# Schematic.net
KiCad netlist of a schematic drawn in EAGLE
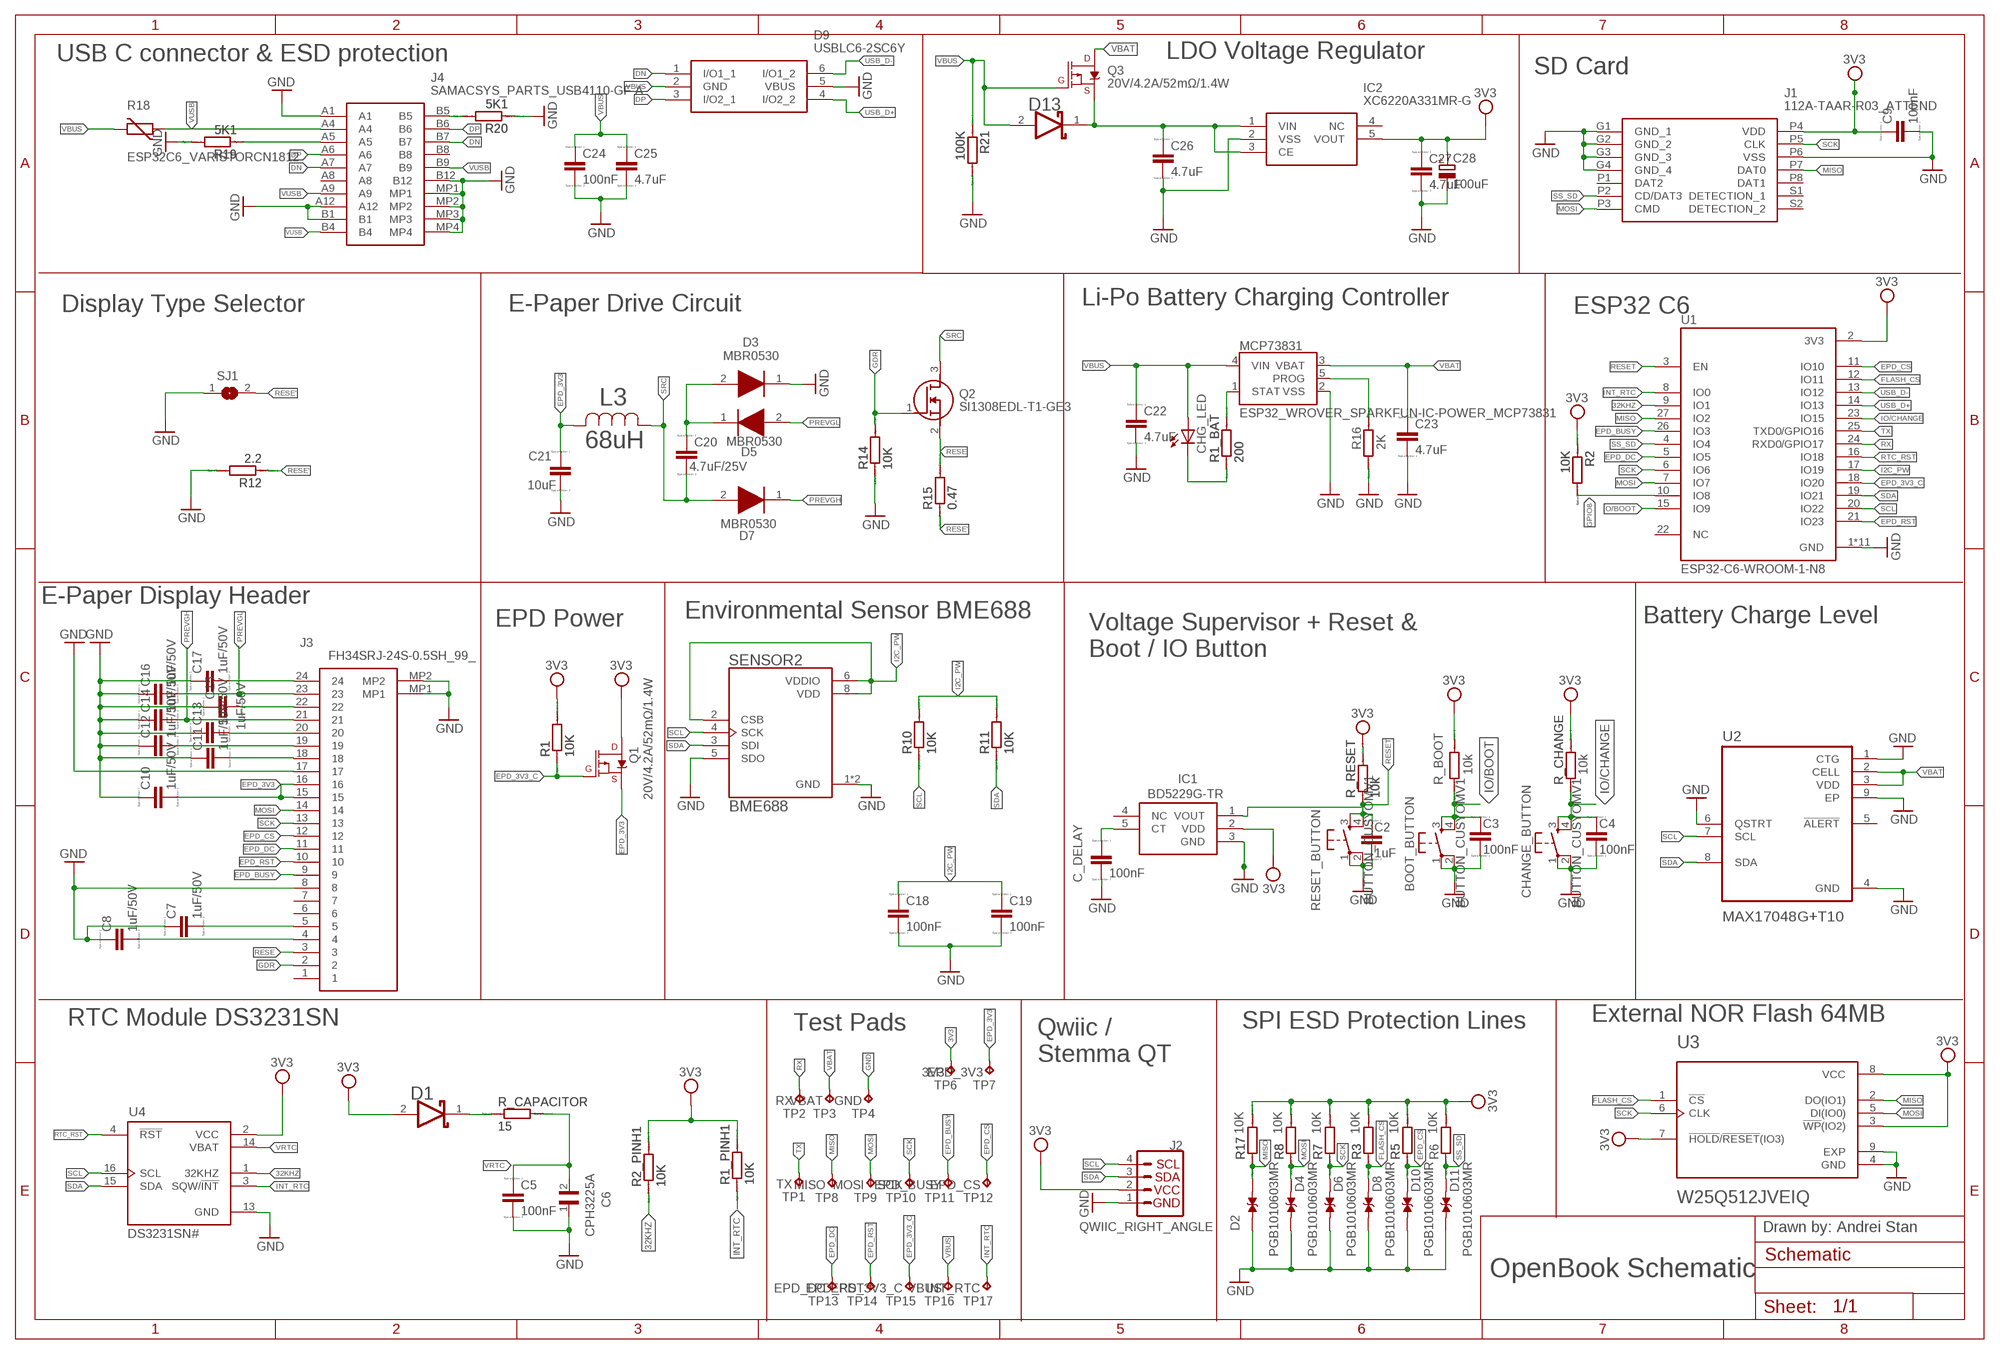
[diagram p0: schematic, sheet 1]

(export (version "E")
  (design (tool "Eeschema 10.0.6"))
  (components
    (comp (ref "BOOT_BUTTON")
      (value "BUTTON_CUSYOMV1")
      (footprint "eagle-import:MYBUTTON")
      (libsource (lib "eagle-import") (part "BUTTON_CUSYOMV1"))
    )
    (comp (ref "C2")
      (value "1uF")
      (footprint "eagle-import:EAGLE-LTSPICE_C0402")
      (libsource (lib "eagle-import") (part "EAGLE-LTSPICE_CC0402"))
    )
    (comp (ref "C3")
      (value "100nF")
      (footprint "eagle-import:EAGLE-LTSPICE_C0402")
      (libsource (lib "eagle-import") (part "EAGLE-LTSPICE_CC0402"))
    )
    (comp (ref "C4")
      (value "100nF")
      (footprint "eagle-import:EAGLE-LTSPICE_C0402")
      (libsource (lib "eagle-import") (part "EAGLE-LTSPICE_CC0402"))
    )
    (comp (ref "C5")
      (value "100nF")
      (footprint "eagle-import:EAGLE-LTSPICE_C0402")
      (libsource (lib "eagle-import") (part "EAGLE-LTSPICE_CC0402"))
    )
    (comp (ref "C6")
      (value "CPH3225A")
      (footprint "eagle-import:CAPCP3225X100N")
      (fields (field (name "MF") "Seiko Instruments"))
      (libsource (lib "eagle-import") (part "CPH3225A"))
    )
    (comp (ref "C7")
      (value "1uF/50V")
      (footprint "eagle-import:EAGLE-LTSPICE_C0402")
      (libsource (lib "eagle-import") (part "EAGLE-LTSPICE_CC0402"))
    )
    (comp (ref "C8")
      (value "1uF/50V")
      (footprint "eagle-import:EAGLE-LTSPICE_C0402")
      (libsource (lib "eagle-import") (part "EAGLE-LTSPICE_CC0402"))
    )
    (comp (ref "C9")
      (value "100nF")
      (footprint "eagle-import:EAGLE-LTSPICE_C0402")
      (libsource (lib "eagle-import") (part "EAGLE-LTSPICE_CC0402"))
    )
    (comp (ref "C10")
      (value "1uF/50V")
      (footprint "eagle-import:EAGLE-LTSPICE_C0402")
      (libsource (lib "eagle-import") (part "EAGLE-LTSPICE_CC0402"))
    )
    (comp (ref "C11")
      (value "1uF/50V")
      (footprint "eagle-import:EAGLE-LTSPICE_C0402")
      (libsource (lib "eagle-import") (part "EAGLE-LTSPICE_CC0402"))
    )
    (comp (ref "C12")
      (value "1uF/50V")
      (footprint "eagle-import:EAGLE-LTSPICE_C0402")
      (libsource (lib "eagle-import") (part "EAGLE-LTSPICE_CC0402"))
    )
    (comp (ref "C13")
      (value "1uF/50V")
      (footprint "eagle-import:EAGLE-LTSPICE_C0402")
      (libsource (lib "eagle-import") (part "EAGLE-LTSPICE_CC0402"))
    )
    (comp (ref "C14")
      (value "1uF/50V")
      (footprint "eagle-import:EAGLE-LTSPICE_C0402")
      (libsource (lib "eagle-import") (part "EAGLE-LTSPICE_CC0402"))
    )
    (comp (ref "C15")
      (value "1uF/50V")
      (footprint "eagle-import:EAGLE-LTSPICE_C0402")
      (libsource (lib "eagle-import") (part "EAGLE-LTSPICE_CC0402"))
    )
    (comp (ref "C16")
      (value "1uF/50V")
      (footprint "eagle-import:EAGLE-LTSPICE_C0402")
      (libsource (lib "eagle-import") (part "EAGLE-LTSPICE_CC0402"))
    )
    (comp (ref "C17")
      (value "1uF/50V")
      (footprint "eagle-import:EAGLE-LTSPICE_C0402")
      (libsource (lib "eagle-import") (part "EAGLE-LTSPICE_CC0402"))
    )
    (comp (ref "C18")
      (value "100nF")
      (footprint "eagle-import:EAGLE-LTSPICE_C0402")
      (libsource (lib "eagle-import") (part "EAGLE-LTSPICE_CC0402"))
    )
    (comp (ref "C19")
      (value "100nF")
      (footprint "eagle-import:EAGLE-LTSPICE_C0402")
      (libsource (lib "eagle-import") (part "EAGLE-LTSPICE_CC0402"))
    )
    (comp (ref "C20")
      (value "4.7uF/25V")
      (footprint "eagle-import:ESP32_WROVER_EAGLE-LTSPICE_C0402")
      (libsource (lib "eagle-import") (part "ESP32_WROVER_EAGLE-LTSPICE_CC0402"))
    )
    (comp (ref "C21")
      (value "10uF")
      (footprint "eagle-import:ESP32_WROVER_EAGLE-LTSPICE_C0402")
      (libsource (lib "eagle-import") (part "ESP32_WROVER_EAGLE-LTSPICE_CC0402"))
    )
    (comp (ref "C22")
      (value "4.7uF")
      (footprint "eagle-import:EAGLE-LTSPICE_C0402")
      (libsource (lib "eagle-import") (part "EAGLE-LTSPICE_CC0402"))
    )
    (comp (ref "C23")
      (value "4.7uF")
      (footprint "eagle-import:EAGLE-LTSPICE_C0402")
      (libsource (lib "eagle-import") (part "EAGLE-LTSPICE_CC0402"))
    )
    (comp (ref "C24")
      (value "100nF")
      (footprint "eagle-import:ESP32_WROVER_EAGLE-LTSPICE_C0402")
      (libsource (lib "eagle-import") (part "ESP32_WROVER_EAGLE-LTSPICE_CC0402"))
    )
    (comp (ref "C25")
      (value "4.7uF")
      (footprint "eagle-import:ESP32_WROVER_EAGLE-LTSPICE_C0402")
      (libsource (lib "eagle-import") (part "ESP32_WROVER_EAGLE-LTSPICE_CC0402"))
    )
    (comp (ref "C26")
      (value "4.7uF")
      (footprint "eagle-import:ESP32_WROVER_EAGLE-LTSPICE_C0402")
      (libsource (lib "eagle-import") (part "ESP32_WROVER_EAGLE-LTSPICE_CC0402"))
    )
    (comp (ref "C27")
      (value "4.7uF")
      (footprint "eagle-import:ESP32_WROVER_EAGLE-LTSPICE_C0402")
      (libsource (lib "eagle-import") (part "ESP32_WROVER_EAGLE-LTSPICE_CC0402"))
    )
    (comp (ref "C28")
      (value "100uF")
      (footprint "eagle-import:RCL_CT3528")
      (libsource (lib "eagle-import") (part "RCL_CPOL-EUCT3528"))
    )
    (comp (ref "CHANGE_BUTTON")
      (value "BUTTON_CUSYOMV1")
      (footprint "eagle-import:MYBUTTON")
      (libsource (lib "eagle-import") (part "BUTTON_CUSYOMV1"))
    )
    (comp (ref "CHG_LED")
      (value "ADAFRUIT_LEDCHIP-LED0603")
      (footprint "eagle-import:ADAFRUIT_CHIP-LED0603")
      (libsource (lib "eagle-import") (part "ADAFRUIT_LEDCHIP-LED0603"))
    )
    (comp (ref "C_DELAY")
      (value "100nF")
      (footprint "eagle-import:EAGLE-LTSPICE_C0402")
      (libsource (lib "eagle-import") (part "EAGLE-LTSPICE_CC0402"))
    )
    (comp (ref "D1")
      (value "ESP32_WROVER_AVX---SD0805S020S1R0_AVX_SD0805S020S1R0_0_0AVX_SD0805S020S1R0_0_0")
      (footprint "eagle-import:ESP32_WROVER_AVX---SD0805S020S1R0_AVX_SD0805S020S1R0_0")
      (fields
        (field (name "DIGIKEY_PART_NUMBER") "478-7800-1-ND")
        (field (name "MF") "AVX")
        (field (name "MOUSER_PART_NUMBER") "581-SD0805S020S1R0")
      )
      (libsource (lib "eagle-import") (part "ESP32_WROVER_AVX---SD0805S020S1R0_AVX_SD0805S020S1R0_0_0AVX_SD0805S020S1R0_0_0"))
    )
    (comp (ref "D2")
      (value "PGB1010603MR")
      (footprint "eagle-import:DIOC1608X36N")
      (fields (field (name "MF") "Littelfuse Inc."))
      (libsource (lib "eagle-import") (part "PGB1010603MR"))
    )
    (comp (ref "D3")
      (value "MBR0530")
      (footprint "eagle-import:SOD3716X135N")
      (fields (field (name "MF") "ON Semiconductor"))
      (libsource (lib "eagle-import") (part "MBR0530"))
    )
    (comp (ref "D4")
      (value "PGB1010603MR")
      (footprint "eagle-import:DIOC1608X36N")
      (fields (field (name "MF") "Littelfuse Inc."))
      (libsource (lib "eagle-import") (part "PGB1010603MR"))
    )
    (comp (ref "D5")
      (value "MBR0530")
      (footprint "eagle-import:SOD3716X135N")
      (fields (field (name "MF") "ON Semiconductor"))
      (libsource (lib "eagle-import") (part "MBR0530"))
    )
    (comp (ref "D6")
      (value "PGB1010603MR")
      (footprint "eagle-import:DIOC1608X36N")
      (fields (field (name "MF") "Littelfuse Inc."))
      (libsource (lib "eagle-import") (part "PGB1010603MR"))
    )
    (comp (ref "D7")
      (value "MBR0530")
      (footprint "eagle-import:SOD3716X135N")
      (fields (field (name "MF") "ON Semiconductor"))
      (libsource (lib "eagle-import") (part "MBR0530"))
    )
    (comp (ref "D8")
      (value "PGB1010603MR")
      (footprint "eagle-import:DIOC1608X36N")
      (fields (field (name "MF") "Littelfuse Inc."))
      (libsource (lib "eagle-import") (part "PGB1010603MR"))
    )
    (comp (ref "D9")
      (value "USBLC6-2SC6Y")
      (footprint "eagle-import:SOT95P280X145-6N")
      (fields (field (name "MF") "STMicroelectronics"))
      (libsource (lib "eagle-import") (part "USBLC6-2SC6Y"))
    )
    (comp (ref "D10")
      (value "PGB1010603MR")
      (footprint "eagle-import:DIOC1608X36N")
      (fields (field (name "MF") "Littelfuse Inc."))
      (libsource (lib "eagle-import") (part "PGB1010603MR"))
    )
    (comp (ref "D11")
      (value "PGB1010603MR")
      (footprint "eagle-import:DIOC1608X36N")
      (fields (field (name "MF") "Littelfuse Inc."))
      (libsource (lib "eagle-import") (part "PGB1010603MR"))
    )
    (comp (ref "D13")
      (value "ESP32_WROVER_AVX---SD0805S020S1R0_AVX_SD0805S020S1R0_0_0AVX_SD0805S020S1R0_0_0")
      (footprint "eagle-import:ESP32_WROVER_AVX---SD0805S020S1R0_AVX_SD0805S020S1R0_0")
      (fields
        (field (name "DIGIKEY_PART_NUMBER") "478-7800-1-ND")
        (field (name "MF") "AVX")
        (field (name "MOUSER_PART_NUMBER") "581-SD0805S020S1R0")
      )
      (libsource (lib "eagle-import") (part "DeskAssistant v19 v2_vf.c-uWg7zGRE2SlFihlENo6g_ESP32_WROVER_AVX---SD0805S020S1R0_AVX_SD0805S020S1R0_0_0AVX_SD0805S020S1R0_0_0"))
    )
    (comp (ref "IC1")
      (value "BD5229G-TR")
      (footprint "eagle-import:SOT95P280X125-5N")
      (fields (field (name "MOUSER_PART_NUMBER") "755-BD5229G-TR"))
      (libsource (lib "eagle-import") (part "BD5229G-TR"))
    )
    (comp (ref "IC2")
      (value "XC6220A331MR-G")
      (footprint "eagle-import:SOT95P280X120-5N")
      (fields (field (name "MOUSER_PART_NUMBER") "865-XC6220A331MR-G"))
      (libsource (lib "eagle-import") (part "XC6220A331MR-G"))
    )
    (comp (ref "J1")
      (value "112A-TAAR-R03_ATTEND")
      (footprint "eagle-import:112ATAARR03ATTEND")
      (fields (field (name "MANUFACTURER_PART_NUMBER") "112A-TAAR-R03 ATTEND"))
      (libsource (lib "eagle-import") (part "112A-TAAR-R03_ATTEND"))
    )
    (comp (ref "J2")
      (value "QWIIC_RIGHT_ANGLE")
      (footprint "eagle-import:JST04_1MM_RA")
      (libsource (lib "eagle-import") (part "QWIIC_CONNECTORJS-1MM"))
    )
    (comp (ref "J3")
      (value "FH34SRJ-24S-0.5SH_99_")
      (footprint "eagle-import:FH34SRJ24S05SH99")
      (fields
        (field (name "MANUFACTURER_PART_NUMBER") "FH34SRJ-24S-0.5SH(99)")
        (field (name "MOUSER_PART_NUMBER") "798-FH34SRJ24S05SH99")
      )
      (libsource (lib "eagle-import") (part "FH34SRJ-24S-0.5SH_99_"))
    )
    (comp (ref "J4")
      (value "SAMACSYS_PARTS_USB4110-GF-A")
      (footprint "eagle-import:SAMACSYS_PARTS_USB4110GFA")
      (fields
        (field (name "MANUFACTURER_PART_NUMBER") "USB4110-GF-A")
        (field (name "MOUSER_PART_NUMBER") "640-USB4110-GF-A")
      )
      (libsource (lib "eagle-import") (part "SAMACSYS_PARTS_USB4110-GF-A"))
    )
    (comp (ref "L3")
      (value "68uH")
      (footprint "eagle-import:IND_4828-WE-TPC_WRE")
      (fields
        (field (name "MANUFACTURER_PART_NUMBER") "744043680")
        (field (name "COPYRIGHT") "Copyright (C) 2024 Ultra Librarian. All rights reserved.")
      )
      (libsource (lib "eagle-import") (part "744043680IND_4828-WE-TPC_WRE"))
    )
    (comp (ref "MCP73831")
      (value "ESP32_WROVER_SPARKFUN-IC-POWER_MCP73831")
      (footprint "eagle-import:ESP32_WROVER_SPARKFUN-IC-POWER_SOT23-5")
      (libsource (lib "eagle-import") (part "ESP32_WROVER_SPARKFUN-IC-POWER_MCP73831"))
    )
    (comp (ref "Q1")
      (value "20V/4.2A/52mΩ/1.4W")
      (footprint "eagle-import:ESP32_WROVER_SPARKFUN-DISCRETESEMI_SOT23-3")
      (libsource (lib "eagle-import") (part "ESP32_WROVER_SPARKFUN-DISCRETESEMI_MOSFET_PCH-DMG2305UX-7"))
    )
    (comp (ref "Q2")
      (value "SI1308EDL-T1-GE3")
      (footprint "eagle-import:SOT65P210X110-3N")
      (fields (field (name "MF") "Vishay Siliconix"))
      (libsource (lib "eagle-import") (part "SI1308EDL-T1-GE3"))
    )
    (comp (ref "Q3")
      (value "20V/4.2A/52mΩ/1.4W")
      (footprint "eagle-import:ESP32_WROVER_SPARKFUN-DISCRETESEMI_SOT23-3")
      (libsource (lib "eagle-import") (part "DeskAssistant v19 v2_vf.c-uWg7zGRE2SlFihlENo6g_ESP32_WROVER_SPARKFUN-DISCRETESEMI_MOSFET_PCH-DMG2305UX-7"))
    )
    (comp (ref "R1")
      (value "10K")
      (footprint "eagle-import:ESP32_WROVER_EAGLE-LTSPICE_R0402")
      (libsource (lib "eagle-import") (part "ESP32_WROVER_EAGLE-LTSPICE_RR0402"))
    )
    (comp (ref "R1_BAT")
      (value "200")
      (footprint "eagle-import:ESP32_WROVER_EAGLE-LTSPICE_R0402")
      (libsource (lib "eagle-import") (part "ESP32_WROVER_EAGLE-LTSPICE_RR0402"))
    )
    (comp (ref "R1_PINH1")
      (value "10K")
      (footprint "eagle-import:ESP32_WROVER_EAGLE-LTSPICE_R0402")
      (libsource (lib "eagle-import") (part "ESP32_WROVER_EAGLE-LTSPICE_RR0402"))
    )
    (comp (ref "R2")
      (value "10K")
      (footprint "eagle-import:ESP32_WROVER_EAGLE-LTSPICE_R0402")
      (libsource (lib "eagle-import") (part "ESP32_WROVER_EAGLE-LTSPICE_RR0402"))
    )
    (comp (ref "R2_PINH1")
      (value "10K")
      (footprint "eagle-import:ESP32_WROVER_EAGLE-LTSPICE_R0402")
      (libsource (lib "eagle-import") (part "ESP32_WROVER_EAGLE-LTSPICE_RR0402"))
    )
    (comp (ref "R3")
      (value "10K")
      (footprint "eagle-import:ESP32_WROVER_EAGLE-LTSPICE_R0402")
      (libsource (lib "eagle-import") (part "ESP32_WROVER_EAGLE-LTSPICE_RR0402"))
    )
    (comp (ref "R5")
      (value "10K")
      (footprint "eagle-import:ESP32_WROVER_EAGLE-LTSPICE_R0402")
      (libsource (lib "eagle-import") (part "ESP32_WROVER_EAGLE-LTSPICE_RR0402"))
    )
    (comp (ref "R6")
      (value "10K")
      (footprint "eagle-import:ESP32_WROVER_EAGLE-LTSPICE_R0402")
      (libsource (lib "eagle-import") (part "ESP32_WROVER_EAGLE-LTSPICE_RR0402"))
    )
    (comp (ref "R7")
      (value "10K")
      (footprint "eagle-import:ESP32_WROVER_EAGLE-LTSPICE_R0402")
      (libsource (lib "eagle-import") (part "ESP32_WROVER_EAGLE-LTSPICE_RR0402"))
    )
    (comp (ref "R8")
      (value "10K")
      (footprint "eagle-import:ESP32_WROVER_EAGLE-LTSPICE_R0402")
      (libsource (lib "eagle-import") (part "ESP32_WROVER_EAGLE-LTSPICE_RR0402"))
    )
    (comp (ref "R10")
      (value "10K")
      (footprint "eagle-import:ESP32_WROVER_EAGLE-LTSPICE_R0402")
      (libsource (lib "eagle-import") (part "ESP32_WROVER_EAGLE-LTSPICE_RR0402"))
    )
    (comp (ref "R11")
      (value "10K")
      (footprint "eagle-import:ESP32_WROVER_EAGLE-LTSPICE_R0402")
      (libsource (lib "eagle-import") (part "ESP32_WROVER_EAGLE-LTSPICE_RR0402"))
    )
    (comp (ref "R12")
      (value "2.2")
      (footprint "eagle-import:ESP32_WROVER_EAGLE-LTSPICE_R0402")
      (libsource (lib "eagle-import") (part "ESP32_WROVER_EAGLE-LTSPICE_RR0402"))
    )
    (comp (ref "R14")
      (value "10K")
      (footprint "eagle-import:ESP32_WROVER_EAGLE-LTSPICE_R0402")
      (libsource (lib "eagle-import") (part "DeskAssistant v19 v2_vf.c-uWg7zGRE2SlFihlENo6g_ESP32_WROVER_EAGLE-LTSPICE_RR0402"))
    )
    (comp (ref "R15")
      (value "0.47")
      (footprint "eagle-import:ESP32_WROVER_EAGLE-LTSPICE_R0402")
      (libsource (lib "eagle-import") (part "DeskAssistant v19 v2_vf.c-uWg7zGRE2SlFihlENo6g_ESP32_WROVER_EAGLE-LTSPICE_RR0402"))
    )
    (comp (ref "R16")
      (value "2K")
      (footprint "eagle-import:ESP32_WROVER_EAGLE-LTSPICE_R0402")
      (libsource (lib "eagle-import") (part "ESP32_WROVER_EAGLE-LTSPICE_RR0402"))
    )
    (comp (ref "R17")
      (value "10K")
      (footprint "eagle-import:ESP32_WROVER_EAGLE-LTSPICE_R0402")
      (libsource (lib "eagle-import") (part "ESP32_WROVER_EAGLE-LTSPICE_RR0402"))
    )
    (comp (ref "R18")
      (value "ESP32C6_VARISTORCN1812")
      (footprint "eagle-import:ESP32C6_VARISTOR_CT_CN1812")
      (libsource (lib "eagle-import") (part "ESP32C6_VARISTORCN1812"))
    )
    (comp (ref "R19")
      (value "5K1")
      (footprint "eagle-import:ESP32_WROVER_EAGLE-LTSPICE_R0402")
      (libsource (lib "eagle-import") (part "ESP32_WROVER_EAGLE-LTSPICE_RR0402"))
    )
    (comp (ref "R20")
      (value "5K1")
      (footprint "eagle-import:ESP32_WROVER_EAGLE-LTSPICE_R0402")
      (libsource (lib "eagle-import") (part "ESP32_WROVER_EAGLE-LTSPICE_RR0402"))
    )
    (comp (ref "R21")
      (value "100K")
      (footprint "eagle-import:ESP32_WROVER_EAGLE-LTSPICE_R0402")
      (libsource (lib "eagle-import") (part "ESP32_WROVER_EAGLE-LTSPICE_RR0402"))
    )
    (comp (ref "RESET_BUTTON")
      (value "BUTTON_CUSYOMV1")
      (footprint "eagle-import:MYBUTTON")
      (fields
        (field (name "MOUSER_PRICE-STOCK") "https://ro.mouser.com/ProductDetail/Panasonic/EVQ-9P701P?qs=NPkb10g2yLBKCwpELvsGNg%3D%3D")
      )
      (libsource (lib "eagle-import") (part "BUTTON_CUSYOMV1"))
    )
    (comp (ref "R_BOOT")
      (value "10k")
      (footprint "eagle-import:ESP32_WROVER_EAGLE-LTSPICE_R0402")
      (libsource (lib "eagle-import") (part "ESP32_WROVER_EAGLE-LTSPICE_RR0402"))
    )
    (comp (ref "R_CAPACITOR")
      (value "15")
      (footprint "eagle-import:ESP32_WROVER_EAGLE-LTSPICE_R0402")
      (libsource (lib "eagle-import") (part "ESP32_WROVER_EAGLE-LTSPICE_RR0402"))
    )
    (comp (ref "R_CHANGE")
      (value "10k")
      (footprint "eagle-import:ESP32_WROVER_EAGLE-LTSPICE_R0402")
      (libsource (lib "eagle-import") (part "ESP32_WROVER_EAGLE-LTSPICE_RR0402"))
    )
    (comp (ref "R_RESET")
      (value "10k")
      (footprint "eagle-import:ESP32_WROVER_EAGLE-LTSPICE_R0402")
      (libsource (lib "eagle-import") (part "ESP32_WROVER_EAGLE-LTSPICE_RR0402"))
    )
    (comp (ref "SENSOR2")
      (value "BME688")
      (footprint "eagle-import:ESP32_WROVER_BME680_PSON80P300X300X100-8N")
      (fields (field (name "MF") "Bosch Sensortec") (field (name "MP") "BME680"))
      (libsource (lib "eagle-import") (part "ESP32_WROVER_BME680_BME680"))
    )
    (comp (ref "SJ1") (value "SJ") (footprint "eagle-import:SJ") (libsource (lib "eagle-import") (part "SJ")))
    (comp (ref "TP1")
      (value "TPTP20R")
      (footprint "eagle-import:TP20R")
      (fields (field (name "TP_SIGNAL_NAME") "TX"))
      (libsource (lib "eagle-import") (part "TPTP20R"))
    )
    (comp (ref "TP2")
      (value "TPTP20R")
      (footprint "eagle-import:TP20R")
      (fields (field (name "TP_SIGNAL_NAME") "RX"))
      (libsource (lib "eagle-import") (part "TPTP20R"))
    )
    (comp (ref "TP3")
      (value "TPTP20R")
      (footprint "eagle-import:TP20R")
      (fields (field (name "TP_SIGNAL_NAME") "VBAT"))
      (libsource (lib "eagle-import") (part "TPTP20R"))
    )
    (comp (ref "TP4")
      (value "TPTP20R")
      (footprint "eagle-import:TP20R")
      (fields (field (name "TP_SIGNAL_NAME") "GND"))
      (libsource (lib "eagle-import") (part "TPTP20R"))
    )
    (comp (ref "TP6")
      (value "TPTP20R")
      (footprint "eagle-import:TP20R")
      (fields (field (name "TP_SIGNAL_NAME") "3V3"))
      (libsource (lib "eagle-import") (part "TPTP20R"))
    )
    (comp (ref "TP7")
      (value "TPTP20R")
      (footprint "eagle-import:TP20R")
      (fields (field (name "TP_SIGNAL_NAME") "EPD_3V3"))
      (libsource (lib "eagle-import") (part "TPTP20R"))
    )
    (comp (ref "TP8")
      (value "TPTP20R")
      (footprint "eagle-import:TP20R")
      (fields (field (name "TP_SIGNAL_NAME") "MISO"))
      (libsource (lib "eagle-import") (part "TPTP20R"))
    )
    (comp (ref "TP9")
      (value "TPTP20R")
      (footprint "eagle-import:TP20R")
      (fields (field (name "TP_SIGNAL_NAME") "MOSI"))
      (libsource (lib "eagle-import") (part "TPTP20R"))
    )
    (comp (ref "TP10")
      (value "TPTP20R")
      (footprint "eagle-import:TP20R")
      (fields (field (name "TP_SIGNAL_NAME") "SCK"))
      (libsource (lib "eagle-import") (part "TPTP20R"))
    )
    (comp (ref "TP11")
      (value "TPTP20R")
      (footprint "eagle-import:TP20R")
      (fields (field (name "TP_SIGNAL_NAME") "EPD_BUSY"))
      (libsource (lib "eagle-import") (part "TPTP20R"))
    )
    (comp (ref "TP12")
      (value "TPTP20R")
      (footprint "eagle-import:TP20R")
      (fields (field (name "TP_SIGNAL_NAME") "EPD_CS"))
      (libsource (lib "eagle-import") (part "TPTP20R"))
    )
    (comp (ref "TP13")
      (value "TPTP20R")
      (footprint "eagle-import:TP20R")
      (fields (field (name "TP_SIGNAL_NAME") "EPD_DC"))
      (libsource (lib "eagle-import") (part "TPTP20R"))
    )
    (comp (ref "TP14")
      (value "TPTP20R")
      (footprint "eagle-import:TP20R")
      (fields (field (name "TP_SIGNAL_NAME") "EPD_RST"))
      (libsource (lib "eagle-import") (part "TPTP20R"))
    )
    (comp (ref "TP15")
      (value "TPTP20R")
      (footprint "eagle-import:TP20R")
      (fields (field (name "TP_SIGNAL_NAME") "EPD_3V3_C"))
      (libsource (lib "eagle-import") (part "TPTP20R"))
    )
    (comp (ref "TP16")
      (value "TPTP20R")
      (footprint "eagle-import:TP20R")
      (fields (field (name "TP_SIGNAL_NAME") "VBUS"))
      (libsource (lib "eagle-import") (part "TPTP20R"))
    )
    (comp (ref "TP17")
      (value "TPTP20R")
      (footprint "eagle-import:TP20R")
      (fields (field (name "TP_SIGNAL_NAME") "INT_RTC"))
      (libsource (lib "eagle-import") (part "TPTP20R"))
    )
    (comp (ref "U1")
      (value "ESP32-C6-WROOM-1-N8")
      (footprint "eagle-import:XCVR_ESP32-C6-WROOM-1-N8")
      (fields (field (name "MF") "Espressif Systems"))
      (libsource (lib "eagle-import") (part "ESP32-C6-WROOM-1-N8"))
    )
    (comp (ref "U2")
      (value "MAX17048G+T10")
      (footprint "eagle-import:SON50P200X200X80-9N")
      (fields (field (name "MF") "Analog Devices"))
      (libsource (lib "eagle-import") (part "MAX17048G+T10"))
    )
    (comp (ref "U3")
      (value "W25Q512JVEIQ")
      (footprint "eagle-import:SON127P600X800X80-9N")
      (fields (field (name "MF") "Winbond Electronics"))
      (libsource (lib "eagle-import") (part "W25Q512JVEIQ"))
    )
    (comp (ref "U4")
      (value "DS3231SN#")
      (footprint "eagle-import:SOIC127P1032X265-16N")
      (fields (field (name "MF") "Analog Devices"))
      (libsource (lib "eagle-import") (part "DS3231SN#"))
    )
  )
  (nets
    (net (code "1") (name "3V3") (class "Default")
      (node (ref "C27") (pin "1") (pinfunction "1_1") (pintype "passive"))
      (node (ref "C28") (pin "+") (pinfunction "+_+") (pintype "passive"))
      (node (ref "C9") (pin "1") (pinfunction "1_1") (pintype "passive"))
      (node (ref "D1") (pin "2") (pinfunction "ANODE_2") (pintype "bidirectional"))
      (node (ref "IC1") (pin "2") (pinfunction "VDD_2") (pintype "bidirectional"))
      (node (ref "IC2") (pin "5") (pinfunction "VOUT_5") (pintype "bidirectional"))
      (node (ref "J1") (pin "P4") (pinfunction "VDD_P4") (pintype "bidirectional"))
      (node (ref "J2") (pin "2") (pinfunction "2_2") (pintype "power_in"))
      (node (ref "Q1") (pin "3") (pinfunction "D_3") (pintype "bidirectional"))
      (node (ref "R1") (pin "2") (pinfunction "2_2") (pintype "passive"))
      (node (ref "R17") (pin "2") (pinfunction "2_2") (pintype "passive"))
      (node (ref "R1_PINH1") (pin "2") (pinfunction "2_2") (pintype "passive"))
      (node (ref "R2") (pin "1") (pinfunction "1_1") (pintype "passive"))
      (node (ref "R2_PINH1") (pin "2") (pinfunction "2_2") (pintype "passive"))
      (node (ref "R3") (pin "2") (pinfunction "2_2") (pintype "passive"))
      (node (ref "R5") (pin "2") (pinfunction "2_2") (pintype "passive"))
      (node (ref "R6") (pin "2") (pinfunction "2_2") (pintype "passive"))
      (node (ref "R7") (pin "2") (pinfunction "2_2") (pintype "passive"))
      (node (ref "R8") (pin "2") (pinfunction "2_2") (pintype "passive"))
      (node (ref "R_BOOT") (pin "2") (pinfunction "2_2") (pintype "passive"))
      (node (ref "R_CHANGE") (pin "2") (pinfunction "2_2") (pintype "passive"))
      (node (ref "R_RESET") (pin "2") (pinfunction "2_2") (pintype "passive"))
      (node (ref "TP6") (pin "TP") (pinfunction "TP_TP") (pintype "input"))
      (node (ref "U1") (pin "2") (pinfunction "3V3_2") (pintype "power_in"))
      (node (ref "U3") (pin "3") (pinfunction "~{WP}(IO2)_3") (pintype "bidirectional"))
      (node (ref "U3") (pin "7") (pinfunction "~{HOLD}/~{RESET}(IO3)_7") (pintype "bidirectional"))
      (node (ref "U3") (pin "8") (pinfunction "VCC_8") (pintype "power_in"))
      (node (ref "U4") (pin "2") (pinfunction "VCC_2") (pintype "power_in"))
    )
    (net (code "2") (name "32KHZ") (class "Default")
      (node (ref "R2_PINH1") (pin "1") (pinfunction "1_1") (pintype "passive"))
      (node (ref "U1") (pin "9") (pinfunction "IO1_9") (pintype "bidirectional"))
      (node (ref "U4") (pin "1") (pinfunction "32KHZ_1") (pintype "output"))
    )
    (net (code "3") (name "DN") (class "Default")
      (node (ref "D9") (pin "1") (pinfunction "I/O1_1_1") (pintype "bidirectional"))
      (node (ref "J4") (pin "A7") (pinfunction "A7_A7") (pintype "bidirectional"))
      (node (ref "J4") (pin "B7") (pinfunction "B7_B7") (pintype "bidirectional"))
    )
    (net (code "4") (name "DP") (class "Default")
      (node (ref "D9") (pin "3") (pinfunction "I/O2_1_3") (pintype "bidirectional"))
      (node (ref "J4") (pin "A6") (pinfunction "A6_A6") (pintype "bidirectional"))
      (node (ref "J4") (pin "B6") (pinfunction "B6_B6") (pintype "bidirectional"))
    )
    (net (code "5") (name "EPD_3V3") (class "Default")
      (node (ref "C10") (pin "2") (pinfunction "2_2") (pintype "passive"))
      (node (ref "C21") (pin "1") (pinfunction "1_1") (pintype "passive"))
      (node (ref "J3") (pin "15") (pinfunction "15_15") (pintype "bidirectional"))
      (node (ref "J3") (pin "16") (pinfunction "16_16") (pintype "bidirectional"))
      (node (ref "L3") (pin "2") (pinfunction "2_2") (pintype "passive"))
      (node (ref "Q1") (pin "2") (pinfunction "S_2") (pintype "bidirectional"))
      (node (ref "TP7") (pin "TP") (pinfunction "TP_TP") (pintype "input"))
    )
    (net (code "6") (name "EPD_3V3_C") (class "Default")
      (node (ref "Q1") (pin "1") (pinfunction "G_1") (pintype "bidirectional"))
      (node (ref "R1") (pin "1") (pinfunction "1_1") (pintype "passive"))
      (node (ref "TP15") (pin "TP") (pinfunction "TP_TP") (pintype "input"))
      (node (ref "U1") (pin "18") (pinfunction "IO20_18") (pintype "bidirectional"))
    )
    (net (code "7") (name "EPD_BUSY") (class "Default")
      (node (ref "J3") (pin "9") (pinfunction "9_9") (pintype "bidirectional"))
      (node (ref "TP11") (pin "TP") (pinfunction "TP_TP") (pintype "input"))
      (node (ref "U1") (pin "26") (pinfunction "IO3_26") (pintype "bidirectional"))
    )
    (net (code "8") (name "EPD_CS") (class "Default")
      (node (ref "D10") (pin "2") (pinfunction "2_2") (pintype "passive"))
      (node (ref "J3") (pin "12") (pinfunction "12_12") (pintype "bidirectional"))
      (node (ref "R5") (pin "1") (pinfunction "1_1") (pintype "passive"))
      (node (ref "TP12") (pin "TP") (pinfunction "TP_TP") (pintype "input"))
      (node (ref "U1") (pin "11") (pinfunction "IO10_11") (pintype "bidirectional"))
    )
    (net (code "9") (name "EPD_DC") (class "Default")
      (node (ref "J3") (pin "11") (pinfunction "11_11") (pintype "bidirectional"))
      (node (ref "TP13") (pin "TP") (pinfunction "TP_TP") (pintype "input"))
      (node (ref "U1") (pin "5") (pinfunction "IO5_5") (pintype "bidirectional"))
    )
    (net (code "10") (name "EPD_RST") (class "Default")
      (node (ref "J3") (pin "10") (pinfunction "10_10") (pintype "bidirectional"))
      (node (ref "TP14") (pin "TP") (pinfunction "TP_TP") (pintype "input"))
      (node (ref "U1") (pin "21") (pinfunction "IO23_21") (pintype "bidirectional"))
    )
    (net (code "11") (name "FLASH_CS") (class "Default")
      (node (ref "D8") (pin "2") (pinfunction "2_2") (pintype "passive"))
      (node (ref "R3") (pin "1") (pinfunction "1_1") (pintype "passive"))
      (node (ref "U1") (pin "12") (pinfunction "IO11_12") (pintype "bidirectional"))
      (node (ref "U3") (pin "1") (pinfunction "~{CS}_1") (pintype "input"))
    )
    (net (code "12") (name "GDR") (class "Default")
      (node (ref "J3") (pin "2") (pinfunction "2_2") (pintype "bidirectional"))
      (node (ref "Q2") (pin "1") (pinfunction "G_1") (pintype "bidirectional"))
      (node (ref "R14") (pin "2") (pinfunction "2_2") (pintype "passive"))
    )
    (net (code "13") (name "GND") (class "Default")
      (node (ref "BOOT_BUTTON") (pin "1") (pinfunction "1_1") (pintype "passive"))
      (node (ref "BOOT_BUTTON") (pin "2") (pinfunction "2_2") (pintype "passive"))
      (node (ref "C10") (pin "1") (pinfunction "1_1") (pintype "passive"))
      (node (ref "C11") (pin "1") (pinfunction "1_1") (pintype "passive"))
      (node (ref "C12") (pin "1") (pinfunction "1_1") (pintype "passive"))
      (node (ref "C13") (pin "1") (pinfunction "1_1") (pintype "passive"))
      (node (ref "C14") (pin "1") (pinfunction "1_1") (pintype "passive"))
      (node (ref "C15") (pin "1") (pinfunction "1_1") (pintype "passive"))
      (node (ref "C16") (pin "1") (pinfunction "1_1") (pintype "passive"))
      (node (ref "C17") (pin "1") (pinfunction "1_1") (pintype "passive"))
      (node (ref "C18") (pin "2") (pinfunction "2_2") (pintype "passive"))
      (node (ref "C19") (pin "2") (pinfunction "2_2") (pintype "passive"))
      (node (ref "C2") (pin "2") (pinfunction "2_2") (pintype "passive"))
      (node (ref "C21") (pin "2") (pinfunction "2_2") (pintype "passive"))
      (node (ref "C22") (pin "2") (pinfunction "2_2") (pintype "passive"))
      (node (ref "C23") (pin "2") (pinfunction "2_2") (pintype "passive"))
      (node (ref "C24") (pin "2") (pinfunction "2_2") (pintype "passive"))
      (node (ref "C25") (pin "2") (pinfunction "2_2") (pintype "passive"))
      (node (ref "C26") (pin "2") (pinfunction "2_2") (pintype "passive"))
      (node (ref "C27") (pin "2") (pinfunction "2_2") (pintype "passive"))
      (node (ref "C28") (pin "-") (pinfunction "-_-") (pintype "passive"))
      (node (ref "C3") (pin "2") (pinfunction "2_2") (pintype "passive"))
      (node (ref "C4") (pin "2") (pinfunction "2_2") (pintype "passive"))
      (node (ref "C5") (pin "2") (pinfunction "2_2") (pintype "passive"))
      (node (ref "C6") (pin "1") (pinfunction "1_1") (pintype "passive"))
      (node (ref "C7") (pin "1") (pinfunction "1_1") (pintype "passive"))
      (node (ref "C8") (pin "1") (pinfunction "1_1") (pintype "passive"))
      (node (ref "C9") (pin "2") (pinfunction "2_2") (pintype "passive"))
      (node (ref "CHANGE_BUTTON") (pin "1") (pinfunction "1_1") (pintype "passive"))
      (node (ref "CHANGE_BUTTON") (pin "2") (pinfunction "2_2") (pintype "passive"))
      (node (ref "C_DELAY") (pin "2") (pinfunction "2_2") (pintype "passive"))
      (node (ref "D10") (pin "1") (pinfunction "1_1") (pintype "passive"))
      (node (ref "D11") (pin "1") (pinfunction "1_1") (pintype "passive"))
      (node (ref "D2") (pin "1") (pinfunction "1_1") (pintype "passive"))
      (node (ref "D3") (pin "1") (pinfunction "K_1") (pintype "bidirectional"))
      (node (ref "D4") (pin "1") (pinfunction "1_1") (pintype "passive"))
      (node (ref "D6") (pin "1") (pinfunction "1_1") (pintype "passive"))
      (node (ref "D8") (pin "1") (pinfunction "1_1") (pintype "passive"))
      (node (ref "D9") (pin "5") (pinfunction "VBUS_5") (pintype "bidirectional"))
      (node (ref "IC1") (pin "3") (pinfunction "GND_3") (pintype "bidirectional"))
      (node (ref "IC2") (pin "2") (pinfunction "VSS_2") (pintype "bidirectional"))
      (node (ref "J1") (pin "G1") (pinfunction "GND_1_G1") (pintype "bidirectional"))
      (node (ref "J1") (pin "G2") (pinfunction "GND_2_G2") (pintype "bidirectional"))
      (node (ref "J1") (pin "G3") (pinfunction "GND_3_G3") (pintype "bidirectional"))
      (node (ref "J1") (pin "G4") (pinfunction "GND_4_G4") (pintype "bidirectional"))
      (node (ref "J1") (pin "P6") (pinfunction "VSS_P6") (pintype "bidirectional"))
      (node (ref "J2") (pin "1") (pinfunction "1_1") (pintype "power_in"))
      (node (ref "J3") (pin "17") (pinfunction "17_17") (pintype "bidirectional"))
      (node (ref "J3") (pin "8") (pinfunction "8_8") (pintype "bidirectional"))
      (node (ref "J3") (pin "MP1") (pinfunction "MP1_MP1") (pintype "bidirectional"))
      (node (ref "J3") (pin "MP2") (pinfunction "MP2_MP2") (pintype "bidirectional"))
      (node (ref "J4") (pin "A1") (pinfunction "A1_A1") (pintype "bidirectional"))
      (node (ref "J4") (pin "A12") (pinfunction "A12_A12") (pintype "bidirectional"))
      (node (ref "J4") (pin "B1") (pinfunction "B1_B1") (pintype "bidirectional"))
      (node (ref "J4") (pin "B12") (pinfunction "B12_B12") (pintype "bidirectional"))
      (node (ref "J4") (pin "MP1") (pinfunction "MP1_MP1") (pintype "bidirectional"))
      (node (ref "J4") (pin "MP2") (pinfunction "MP2_MP2") (pintype "bidirectional"))
      (node (ref "J4") (pin "MP3") (pinfunction "MP3_MP3") (pintype "bidirectional"))
      (node (ref "J4") (pin "MP4") (pinfunction "MP4_MP4") (pintype "bidirectional"))
      (node (ref "MCP73831") (pin "2") (pinfunction "VSS_2") (pintype "power_in"))
      (node (ref "R12") (pin "2") (pinfunction "2_2") (pintype "passive"))
      (node (ref "R14") (pin "1") (pinfunction "1_1") (pintype "passive"))
      (node (ref "R16") (pin "1") (pinfunction "1_1") (pintype "passive"))
      (node (ref "R19") (pin "2") (pinfunction "2_2") (pintype "passive"))
      (node (ref "R20") (pin "1") (pinfunction "1_1") (pintype "passive"))
      (node (ref "R21") (pin "2") (pinfunction "2_2") (pintype "passive"))
      (node (ref "RESET_BUTTON") (pin "1") (pinfunction "1_1") (pintype "passive"))
      (node (ref "RESET_BUTTON") (pin "2") (pinfunction "2_2") (pintype "passive"))
      (node (ref "SENSOR2") (pin "1") (pinfunction "GND_1") (pintype "power_in"))
      (node (ref "SENSOR2") (pin "5") (pinfunction "SDO_5") (pintype "bidirectional"))
      (node (ref "SENSOR2") (pin "7") (pinfunction "GND_7") (pintype "power_in"))
      (node (ref "SJ1") (pin "1") (pinfunction "1_1") (pintype "passive"))
      (node (ref "TP4") (pin "TP") (pinfunction "TP_TP") (pintype "input"))
      (node (ref "U1") (pin "1") (pinfunction "GND_1") (pintype "power_in"))
      (node (ref "U1") (pin "28") (pinfunction "GND_28") (pintype "power_in"))
      (node (ref "U1") (pin "29_1") (pinfunction "GND_29_1") (pintype "power_in"))
      (node (ref "U1") (pin "29_2") (pinfunction "GND_29_2") (pintype "power_in"))
      (node (ref "U1") (pin "29_3") (pinfunction "GND_29_3") (pintype "power_in"))
      (node (ref "U1") (pin "29_4") (pinfunction "GND_29_4") (pintype "power_in"))
      (node (ref "U1") (pin "29_5") (pinfunction "GND_29_5") (pintype "power_in"))
      (node (ref "U1") (pin "29_6") (pinfunction "GND_29_6") (pintype "power_in"))
      (node (ref "U1") (pin "29_7") (pinfunction "GND_29_7") (pintype "power_in"))
      (node (ref "U1") (pin "29_8") (pinfunction "GND_29_8") (pintype "power_in"))
      (node (ref "U1") (pin "29_9") (pinfunction "GND_29_9") (pintype "power_in"))
      (node (ref "U2") (pin "1") (pinfunction "CTG_1") (pintype "power_in"))
      (node (ref "U2") (pin "4") (pinfunction "GND_4") (pintype "power_in"))
      (node (ref "U2") (pin "6") (pinfunction "QSTRT_6") (pintype "input"))
      (node (ref "U2") (pin "9") (pinfunction "EP_9") (pintype "power_in"))
      (node (ref "U3") (pin "4") (pinfunction "GND_4") (pintype "power_in"))
      (node (ref "U3") (pin "9") (pinfunction "EXP_9") (pintype "passive"))
      (node (ref "U4") (pin "13") (pinfunction "GND_13") (pintype "power_in"))
    )
    (net (code "14") (name "GPIO8") (class "Default")
      (node (ref "R2") (pin "2") (pinfunction "2_2") (pintype "passive"))
      (node (ref "U1") (pin "10") (pinfunction "IO8_10") (pintype "bidirectional"))
    )
    (net (code "15") (name "I2C_PW") (class "Default")
      (node (ref "C18") (pin "1") (pinfunction "1_1") (pintype "passive"))
      (node (ref "C19") (pin "1") (pinfunction "1_1") (pintype "passive"))
      (node (ref "R10") (pin "2") (pinfunction "2_2") (pintype "passive"))
      (node (ref "R11") (pin "2") (pinfunction "2_2") (pintype "passive"))
      (node (ref "SENSOR2") (pin "2") (pinfunction "CSB_2") (pintype "input"))
      (node (ref "SENSOR2") (pin "6") (pinfunction "VDDIO_6") (pintype "power_in"))
      (node (ref "SENSOR2") (pin "8") (pinfunction "VDD_8") (pintype "power_in"))
      (node (ref "U1") (pin "17") (pinfunction "IO19_17") (pintype "bidirectional"))
    )
    (net (code "16") (name "INT_RTC") (class "Default")
      (node (ref "R1_PINH1") (pin "1") (pinfunction "1_1") (pintype "passive"))
      (node (ref "TP17") (pin "TP") (pinfunction "TP_TP") (pintype "input"))
      (node (ref "U1") (pin "8") (pinfunction "IO0_8") (pintype "bidirectional"))
      (node (ref "U4") (pin "3") (pinfunction "SQW/~{INT}_3") (pintype "output"))
    )
    (net (code "17") (name "IO{slash}BOOT") (class "Default")
      (node (ref "BOOT_BUTTON") (pin "3") (pinfunction "3_3") (pintype "passive"))
      (node (ref "BOOT_BUTTON") (pin "4") (pinfunction "4_4") (pintype "passive"))
      (node (ref "C3") (pin "1") (pinfunction "1_1") (pintype "passive"))
      (node (ref "R_BOOT") (pin "1") (pinfunction "1_1") (pintype "passive"))
      (node (ref "U1") (pin "15") (pinfunction "IO9_15") (pintype "bidirectional"))
    )
    (net (code "18") (name "IO{slash}CHANGE") (class "Default")
      (node (ref "C4") (pin "1") (pinfunction "1_1") (pintype "passive"))
      (node (ref "CHANGE_BUTTON") (pin "3") (pinfunction "3_3") (pintype "passive"))
      (node (ref "CHANGE_BUTTON") (pin "4") (pinfunction "4_4") (pintype "passive"))
      (node (ref "R_CHANGE") (pin "1") (pinfunction "1_1") (pintype "passive"))
      (node (ref "U1") (pin "23") (pinfunction "IO15_23") (pintype "bidirectional"))
    )
    (net (code "19") (name "MISO") (class "Default")
      (node (ref "D2") (pin "2") (pinfunction "2_2") (pintype "passive"))
      (node (ref "J1") (pin "P7") (pinfunction "DAT0_P7") (pintype "bidirectional"))
      (node (ref "R17") (pin "1") (pinfunction "1_1") (pintype "passive"))
      (node (ref "TP8") (pin "TP") (pinfunction "TP_TP") (pintype "input"))
      (node (ref "U1") (pin "27") (pinfunction "IO2_27") (pintype "bidirectional"))
      (node (ref "U3") (pin "2") (pinfunction "DO(IO1)_2") (pintype "bidirectional"))
    )
    (net (code "20") (name "MOSI") (class "Default")
      (node (ref "D4") (pin "2") (pinfunction "2_2") (pintype "passive"))
      (node (ref "J1") (pin "P3") (pinfunction "CMD_P3") (pintype "bidirectional"))
      (node (ref "J3") (pin "14") (pinfunction "14_14") (pintype "bidirectional"))
      (node (ref "R8") (pin "1") (pinfunction "1_1") (pintype "passive"))
      (node (ref "TP9") (pin "TP") (pinfunction "TP_TP") (pintype "input"))
      (node (ref "U1") (pin "7") (pinfunction "IO7_7") (pintype "bidirectional"))
      (node (ref "U3") (pin "5") (pinfunction "DI(IO0)_5") (pintype "bidirectional"))
    )
    (net (code "21") (name "Net-(C7-Pad2)") (class "Default")
      (node (ref "C7") (pin "2") (pinfunction "2_2") (pintype "passive"))
      (node (ref "J3") (pin "5") (pinfunction "5_5") (pintype "bidirectional"))
    )
    (net (code "22") (name "Net-(C8-Pad2)") (class "Default")
      (node (ref "C8") (pin "2") (pinfunction "2_2") (pintype "passive"))
      (node (ref "J3") (pin "4") (pinfunction "4_4") (pintype "bidirectional"))
    )
    (net (code "23") (name "Net-(C11-Pad2)") (class "Default")
      (node (ref "C11") (pin "2") (pinfunction "2_2") (pintype "passive"))
      (node (ref "J3") (pin "18") (pinfunction "18_18") (pintype "bidirectional"))
    )
    (net (code "24") (name "Net-(C12-Pad2)") (class "Default")
      (node (ref "C12") (pin "2") (pinfunction "2_2") (pintype "passive"))
      (node (ref "J3") (pin "19") (pinfunction "19_19") (pintype "bidirectional"))
    )
    (net (code "25") (name "Net-(C13-Pad2)") (class "Default")
      (node (ref "C13") (pin "2") (pinfunction "2_2") (pintype "passive"))
      (node (ref "J3") (pin "20") (pinfunction "20_20") (pintype "bidirectional"))
    )
    (net (code "26") (name "Net-(C15-Pad2)") (class "Default")
      (node (ref "C15") (pin "2") (pinfunction "2_2") (pintype "passive"))
      (node (ref "J3") (pin "22") (pinfunction "22_22") (pintype "bidirectional"))
    )
    (net (code "27") (name "Net-(C17-Pad2)") (class "Default")
      (node (ref "C17") (pin "2") (pinfunction "2_2") (pintype "passive"))
      (node (ref "J3") (pin "24") (pinfunction "24_24") (pintype "bidirectional"))
    )
    (net (code "28") (name "Net-(CHG_LED-PadC)") (class "Default")
      (node (ref "CHG_LED") (pin "C") (pinfunction "C_C") (pintype "passive"))
      (node (ref "R1_BAT") (pin "1") (pinfunction "1_1") (pintype "passive"))
    )
    (net (code "29") (name "Net-(D1-CATHODE)") (class "Default")
      (node (ref "D1") (pin "1") (pinfunction "CATHODE_1") (pintype "bidirectional"))
      (node (ref "R_CAPACITOR") (pin "1") (pinfunction "1_1") (pintype "passive"))
    )
    (net (code "30") (name "Net-(D3-A)") (class "Default")
      (node (ref "C20") (pin "1") (pinfunction "1_1") (pintype "passive"))
      (node (ref "D3") (pin "2") (pinfunction "A_2") (pintype "bidirectional"))
      (node (ref "D5") (pin "1") (pinfunction "K_1") (pintype "bidirectional"))
    )
    (net (code "31") (name "Net-(D13-CATHODE)") (class "Default")
      (node (ref "C26") (pin "1") (pinfunction "1_1") (pintype "passive"))
      (node (ref "D13") (pin "1") (pinfunction "CATHODE_1") (pintype "bidirectional"))
      (node (ref "IC2") (pin "1") (pinfunction "VIN_1") (pintype "bidirectional"))
      (node (ref "IC2") (pin "3") (pinfunction "CE_3") (pintype "bidirectional"))
      (node (ref "Q3") (pin "2") (pinfunction "S_2") (pintype "bidirectional"))
    )
    (net (code "32") (name "Net-(IC1-CT)") (class "Default")
      (node (ref "C_DELAY") (pin "1") (pinfunction "1_1") (pintype "passive"))
      (node (ref "IC1") (pin "5") (pinfunction "CT_5") (pintype "bidirectional"))
    )
    (net (code "33") (name "Net-(J4-PadA5)") (class "Default")
      (node (ref "J4") (pin "A5") (pinfunction "A5_A5") (pintype "bidirectional"))
      (node (ref "R19") (pin "1") (pinfunction "1_1") (pintype "passive"))
    )
    (net (code "34") (name "Net-(J4-PadB5)") (class "Default")
      (node (ref "J4") (pin "B5") (pinfunction "B5_B5") (pintype "bidirectional"))
      (node (ref "R20") (pin "2") (pinfunction "2_2") (pintype "passive"))
    )
    (net (code "35") (name "Net-(MCP73831-PROG)") (class "Default")
      (node (ref "MCP73831") (pin "5") (pinfunction "PROG_5") (pintype "input"))
      (node (ref "R16") (pin "2") (pinfunction "2_2") (pintype "passive"))
    )
    (net (code "36") (name "Net-(MCP73831-STAT)") (class "Default")
      (node (ref "MCP73831") (pin "1") (pinfunction "STAT_1") (pintype "output"))
      (node (ref "R1_BAT") (pin "2") (pinfunction "2_2") (pintype "passive"))
    )
    (net (code "37") (name "PREVGH") (class "Default")
      (node (ref "C14") (pin "2") (pinfunction "2_2") (pintype "passive"))
      (node (ref "D7") (pin "1") (pinfunction "K_1") (pintype "bidirectional"))
      (node (ref "J3") (pin "21") (pinfunction "21_21") (pintype "bidirectional"))
    )
    (net (code "38") (name "PREVGL") (class "Default")
      (node (ref "C16") (pin "2") (pinfunction "2_2") (pintype "passive"))
      (node (ref "D5") (pin "2") (pinfunction "A_2") (pintype "bidirectional"))
      (node (ref "J3") (pin "23") (pinfunction "23_23") (pintype "bidirectional"))
    )
    (net (code "39") (name "RESE") (class "Default")
      (node (ref "J3") (pin "3") (pinfunction "3_3") (pintype "bidirectional"))
      (node (ref "Q2") (pin "2") (pinfunction "S_2") (pintype "bidirectional"))
      (node (ref "R15") (pin "2") (pinfunction "2_2") (pintype "passive"))
    )
    (net (code "40") (name "RESE'") (class "Default")
      (node (ref "R12") (pin "1") (pinfunction "1_1") (pintype "passive"))
      (node (ref "R15") (pin "1") (pinfunction "1_1") (pintype "passive"))
      (node (ref "SJ1") (pin "2") (pinfunction "2_2") (pintype "passive"))
    )
    (net (code "41") (name "RESET") (class "Default")
      (node (ref "C2") (pin "1") (pinfunction "1_1") (pintype "passive"))
      (node (ref "IC1") (pin "1") (pinfunction "VOUT_1") (pintype "bidirectional"))
      (node (ref "RESET_BUTTON") (pin "3") (pinfunction "3_3") (pintype "passive"))
      (node (ref "RESET_BUTTON") (pin "4") (pinfunction "4_4") (pintype "passive"))
      (node (ref "R_RESET") (pin "1") (pinfunction "1_1") (pintype "passive"))
      (node (ref "U1") (pin "3") (pinfunction "EN_3") (pintype "input"))
    )
    (net (code "42") (name "RTC_RST") (class "Default")
      (node (ref "U1") (pin "16") (pinfunction "IO18_16") (pintype "bidirectional"))
      (node (ref "U4") (pin "4") (pinfunction "~{RST}_4") (pintype "input"))
    )
    (net (code "43") (name "RX") (class "Default")
      (node (ref "TP2") (pin "TP") (pinfunction "TP_TP") (pintype "input"))
      (node (ref "U1") (pin "24") (pinfunction "RXD0/GPIO17_24") (pintype "bidirectional"))
    )
    (net (code "44") (name "SCK") (class "Default")
      (node (ref "D6") (pin "2") (pinfunction "2_2") (pintype "passive"))
      (node (ref "J1") (pin "P5") (pinfunction "CLK_P5") (pintype "bidirectional"))
      (node (ref "J3") (pin "13") (pinfunction "13_13") (pintype "bidirectional"))
      (node (ref "R7") (pin "1") (pinfunction "1_1") (pintype "passive"))
      (node (ref "TP10") (pin "TP") (pinfunction "TP_TP") (pintype "input"))
      (node (ref "U1") (pin "6") (pinfunction "IO6_6") (pintype "bidirectional"))
      (node (ref "U3") (pin "6") (pinfunction "CLK_6") (pintype "input"))
    )
    (net (code "45") (name "SCL") (class "Default")
      (node (ref "J2") (pin "4") (pinfunction "4_4") (pintype "passive"))
      (node (ref "R10") (pin "1") (pinfunction "1_1") (pintype "passive"))
      (node (ref "SENSOR2") (pin "4") (pinfunction "SCK_4") (pintype "input"))
      (node (ref "U1") (pin "20") (pinfunction "IO22_20") (pintype "bidirectional"))
      (node (ref "U2") (pin "7") (pinfunction "SCL_7") (pintype "input"))
      (node (ref "U4") (pin "16") (pinfunction "SCL_16") (pintype "input"))
    )
    (net (code "46") (name "SDA") (class "Default")
      (node (ref "J2") (pin "3") (pinfunction "3_3") (pintype "passive"))
      (node (ref "R11") (pin "1") (pinfunction "1_1") (pintype "passive"))
      (node (ref "SENSOR2") (pin "3") (pinfunction "SDI_3") (pintype "bidirectional"))
      (node (ref "U1") (pin "19") (pinfunction "IO21_19") (pintype "bidirectional"))
      (node (ref "U2") (pin "8") (pinfunction "SDA_8") (pintype "bidirectional"))
      (node (ref "U4") (pin "15") (pinfunction "SDA_15") (pintype "bidirectional"))
    )
    (net (code "47") (name "SRC") (class "Default")
      (node (ref "C20") (pin "2") (pinfunction "2_2") (pintype "passive"))
      (node (ref "D7") (pin "2") (pinfunction "A_2") (pintype "bidirectional"))
      (node (ref "L3") (pin "1") (pinfunction "1_1") (pintype "passive"))
      (node (ref "Q2") (pin "3") (pinfunction "D_3") (pintype "bidirectional"))
    )
    (net (code "48") (name "SS_SD") (class "Default")
      (node (ref "D11") (pin "2") (pinfunction "2_2") (pintype "passive"))
      (node (ref "J1") (pin "P2") (pinfunction "CD/DAT3_P2") (pintype "bidirectional"))
      (node (ref "R6") (pin "1") (pinfunction "1_1") (pintype "passive"))
      (node (ref "U1") (pin "4") (pinfunction "IO4_4") (pintype "bidirectional"))
    )
    (net (code "49") (name "TX") (class "Default")
      (node (ref "TP1") (pin "TP") (pinfunction "TP_TP") (pintype "input"))
      (node (ref "U1") (pin "25") (pinfunction "TXD0/GPIO16_25") (pintype "bidirectional"))
    )
    (net (code "50") (name "USB_D+") (class "Default")
      (node (ref "D9") (pin "4") (pinfunction "I/O2_2_4") (pintype "bidirectional"))
      (node (ref "U1") (pin "14") (pinfunction "IO13_14") (pintype "bidirectional"))
    )
    (net (code "51") (name "USB_D-") (class "Default")
      (node (ref "D9") (pin "6") (pinfunction "I/O1_2_6") (pintype "bidirectional"))
      (node (ref "U1") (pin "13") (pinfunction "IO12_13") (pintype "bidirectional"))
    )
    (net (code "52") (name "VBAT") (class "Default")
      (node (ref "C23") (pin "1") (pinfunction "1_1") (pintype "passive"))
      (node (ref "MCP73831") (pin "3") (pinfunction "VBAT_3") (pintype "power_in"))
      (node (ref "Q3") (pin "3") (pinfunction "D_3") (pintype "bidirectional"))
      (node (ref "TP3") (pin "TP") (pinfunction "TP_TP") (pintype "input"))
      (node (ref "U2") (pin "2") (pinfunction "CELL_2") (pintype "power_in"))
      (node (ref "U2") (pin "3") (pinfunction "VDD_3") (pintype "power_in"))
    )
    (net (code "53") (name "VBUS") (class "Default")
      (node (ref "C22") (pin "1") (pinfunction "1_1") (pintype "passive"))
      (node (ref "C24") (pin "1") (pinfunction "1_1") (pintype "passive"))
      (node (ref "C25") (pin "1") (pinfunction "1_1") (pintype "passive"))
      (node (ref "CHG_LED") (pin "A") (pinfunction "A_A") (pintype "passive"))
      (node (ref "D13") (pin "2") (pinfunction "ANODE_2") (pintype "bidirectional"))
      (node (ref "D9") (pin "2") (pinfunction "GND_2") (pintype "bidirectional"))
      (node (ref "MCP73831") (pin "4") (pinfunction "VIN_4") (pintype "power_in"))
      (node (ref "Q3") (pin "1") (pinfunction "G_1") (pintype "bidirectional"))
      (node (ref "R18") (pin "2") (pinfunction "2_2") (pintype "passive"))
      (node (ref "R21") (pin "1") (pinfunction "1_1") (pintype "passive"))
      (node (ref "TP16") (pin "TP") (pinfunction "TP_TP") (pintype "input"))
    )
    (net (code "54") (name "VRTC") (class "Default")
      (node (ref "C5") (pin "1") (pinfunction "1_1") (pintype "passive"))
      (node (ref "C6") (pin "2") (pinfunction "2_2") (pintype "passive"))
      (node (ref "R_CAPACITOR") (pin "2") (pinfunction "2_2") (pintype "passive"))
      (node (ref "U4") (pin "14") (pinfunction "VBAT_14") (pintype "power_in"))
    )
    (net (code "55") (name "VUSB") (class "Default")
      (node (ref "J4") (pin "A4") (pinfunction "A4_A4") (pintype "bidirectional"))
      (node (ref "J4") (pin "A9") (pinfunction "A9_A9") (pintype "bidirectional"))
      (node (ref "J4") (pin "B4") (pinfunction "B4_B4") (pintype "bidirectional"))
      (node (ref "J4") (pin "B9") (pinfunction "B9_B9") (pintype "bidirectional"))
      (node (ref "R18") (pin "1") (pinfunction "1_1") (pintype "passive"))
    )
    (net (code "56") (name "unconnected-(IC1-NC-Pad4)") (class "Default")
      (node (ref "IC1") (pin "4") (pinfunction "NC_4") (pintype "no_connect"))
    )
    (net (code "57") (name "unconnected-(IC2-NC-Pad4)") (class "Default")
      (node (ref "IC2") (pin "4") (pinfunction "NC_4") (pintype "no_connect"))
    )
    (net (code "58") (name "unconnected-(J1-DAT1-PadP8)") (class "Default")
      (node (ref "J1") (pin "P8") (pinfunction "DAT1_P8") (pintype "bidirectional"))
    )
    (net (code "59") (name "unconnected-(J1-DAT2-PadP1)") (class "Default")
      (node (ref "J1") (pin "P1") (pinfunction "DAT2_P1") (pintype "bidirectional"))
    )
    (net (code "60") (name "unconnected-(J1-DETECTION_1-PadS1)") (class "Default")
      (node (ref "J1") (pin "S1") (pinfunction "DETECTION_1_S1") (pintype "bidirectional"))
    )
    (net (code "61") (name "unconnected-(J1-DETECTION_2-PadS2)") (class "Default")
      (node (ref "J1") (pin "S2") (pinfunction "DETECTION_2_S2") (pintype "bidirectional"))
    )
    (net (code "62") (name "unconnected-(J3-Pad1)") (class "Default")
      (node (ref "J3") (pin "1") (pinfunction "1_1") (pintype "bidirectional"))
    )
    (net (code "63") (name "unconnected-(J3-Pad6)") (class "Default")
      (node (ref "J3") (pin "6") (pinfunction "6_6") (pintype "bidirectional"))
    )
    (net (code "64") (name "unconnected-(J3-Pad7)") (class "Default")
      (node (ref "J3") (pin "7") (pinfunction "7_7") (pintype "bidirectional"))
    )
    (net (code "65") (name "unconnected-(J4-PadA8)") (class "Default")
      (node (ref "J4") (pin "A8") (pinfunction "A8_A8") (pintype "bidirectional"))
    )
    (net (code "66") (name "unconnected-(J4-PadB8)") (class "Default")
      (node (ref "J4") (pin "B8") (pinfunction "B8_B8") (pintype "bidirectional"))
    )
    (net (code "67") (name "unconnected-(U1-NC-Pad22)") (class "Default")
      (node (ref "U1") (pin "22") (pinfunction "NC_22") (pintype "no_connect"))
    )
    (net (code "68") (name "unconnected-(U2-~{ALERT}-Pad5)") (class "Default")
      (node (ref "U2") (pin "5") (pinfunction "~{ALERT}_5") (pintype "output"))
    )
  )
)
